# config.net
KiCad netlist of a schematic drawn in Altium Designer
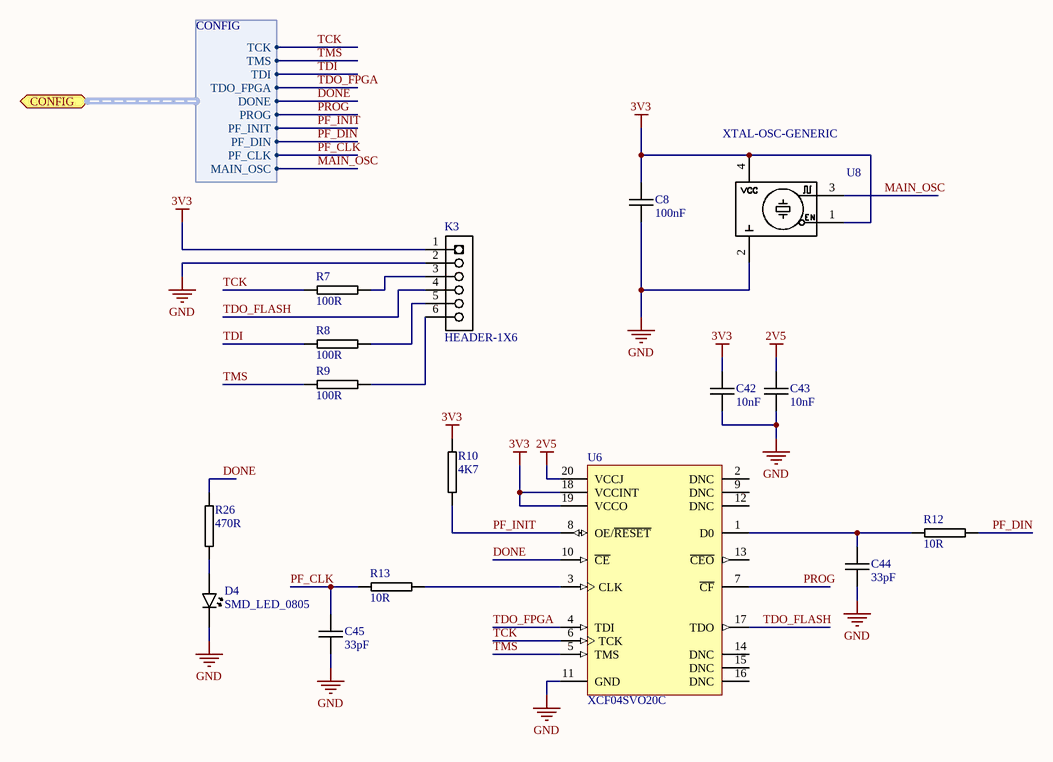
[diagram p0: config.SchDoc]

(export (version "E")
  (design (tool "Eeschema 10.0.6"))
  (components
    (comp (ref "C8")
      (value "100nF")
      (footprint "0603C-GENERIC")
      (description "GENERIC CAPACITOR NON POLARISED 0603")
      (fields (field (name "TOLERANCE") "±10%") (field (name "MANUFACTURER PART NUMBER") "C1608X7R1H103K"))
      (libsource (lib "vh_Altium Library") (part "0603C-100NF-50V-X7R-TDK"))
    )
    (comp (ref "C42")
      (value "10nF")
      (footprint "0603C-GENERIC")
      (description "GENERIC CAPACITOR NON POLARISED 0603")
      (fields
        (field (name "MANUFACTURER PART NUMBER") "GRM188R71H103KA01D")
        (field (name "MANUFACTURER") "Murata Electronics North America")
      )
      (libsource (lib "vh_Altium Library") (part "0603C-10NF-50V-X7R-MUR"))
    )
    (comp (ref "C43")
      (value "10nF")
      (footprint "0603C-GENERIC")
      (description "GENERIC CAPACITOR NON POLARISED 0603")
      (fields
        (field (name "MANUFACTURER PART NUMBER") "GRM188R71H103KA01D")
        (field (name "MANUFACTURER") "Murata Electronics North America")
      )
      (libsource (lib "vh_Altium Library") (part "0603C-10NF-50V-X7R-MUR"))
    )
    (comp (ref "C44")
      (value "33pF")
      (footprint "0603C-GENERIC")
      (description "GENERIC CAPACITOR NON POLARISED 0603")
      (libsource (lib "vh_Altium Library") (part "0603C-33PF-50V-C0G-PAN"))
    )
    (comp (ref "C45")
      (value "33pF")
      (footprint "0603C-GENERIC")
      (description "GENERIC CAPACITOR NON POLARISED 0603")
      (libsource (lib "vh_Altium Library") (part "0603C-33PF-50V-C0G-PAN"))
    )
    (comp (ref "D4")
      (value "SMD_LED_0805")
      (footprint "CD2012-0805")
      (libsource (lib "camera_board") (part "SMD_LED_0805"))
    )
    (comp (ref "K3")
      (value "HEADER-1X6")
      (footprint "HEADER-1X6")
      (libsource (lib "vh_Altium Library") (part "HEADER-1X6"))
    )
    (comp (ref "R7")
      (value "100R")
      (footprint "0603R-100")
      (description "RES 100 OHM 1/10W 1% 0603 SMD")
      (fields (field (name "MANUFACTURER PART NUMBER") "RMCF 1/16 100 1% R"))
      (libsource (lib "vh_Altium Library") (part "0603R-100"))
    )
    (comp (ref "R8")
      (value "100R")
      (footprint "0603R-100")
      (description "RES 100 OHM 1/10W 1% 0603 SMD")
      (fields (field (name "MANUFACTURER PART NUMBER") "RMCF 1/16 100 1% R"))
      (libsource (lib "vh_Altium Library") (part "0603R-100"))
    )
    (comp (ref "R9")
      (value "100R")
      (footprint "0603R-100")
      (description "RES 100 OHM 1/10W 1% 0603 SMD")
      (fields (field (name "MANUFACTURER PART NUMBER") "RMCF 1/16 100 1% R"))
      (libsource (lib "vh_Altium Library") (part "0603R-100"))
    )
    (comp (ref "R10")
      (value "4K7")
      (footprint "0603R-4K7")
      (description "GENERIC RESISTOR 0603")
      (fields
        (field (name "MANUFACTURER") "Stackpole Electronics Inc")
        (field (name "MANUFACTURER PART NUMBER") "RMCF 1/16 4.7K 1% R")
      )
      (libsource (lib "vh_Altium Library") (part "0603R-4K7"))
    )
    (comp (ref "R12")
      (value "10R")
      (footprint "0603R-10")
      (description "GENERIC RESISTOR 0603")
      (fields
        (field (name "MANUFACTURER PART NUMBER") "RMCF 1/16 10 1% R")
        (field (name "MANUFACTURER") "Stackpole Electronics Inc")
      )
      (libsource (lib "vh_Altium Library") (part "0603R-10R"))
    )
    (comp (ref "R13")
      (value "10R")
      (footprint "0603R-10")
      (description "GENERIC RESISTOR 0603")
      (fields
        (field (name "MANUFACTURER PART NUMBER") "RMCF 1/16 10 1% R")
        (field (name "MANUFACTURER") "Stackpole Electronics Inc")
      )
      (libsource (lib "vh_Altium Library") (part "0603R-10R"))
    )
    (comp (ref "R26")
      (value "470R")
      (footprint "0603R-470")
      (description "GENERIC RESISTOR 0603")
      (fields (field (name "MANUFACTURER PART NUMBER") "RMCF 1/16 470 1% R") (field (name "TOLERANCE") "±1%"))
      (libsource (lib "vh_Altium Library") (part "0603R-470"))
    )
    (comp (ref "U6")
      (value "XCF04SVO20C")
      (footprint "VO20_N")
      (fields (field (name "PUBLISHER") "Altium Limited"))
      (libsource (lib "Xilinx XCF") (part "XCF04SVO20C"))
    )
    (comp (ref "U8")
      (value "XTAL-OSC-GENERIC")
      (footprint "XOSC-5X7")
      (description "GENERIC CRYSTAL OSCILLATOR")
      (libsource (lib "vh_Altium Library") (part "XTAL-OSC-GENERIC"))
    )
  )
  (nets
    (net (code "2") (name "/DONE") (class "Default")
      (node (ref "R26") (pin "1") (pintype "passive"))
      (node (ref "U6") (pin "10") (pinfunction "~{CE}_10") (pintype "input"))
    )
    (net (code "3") (name "/MAIN_OSC") (class "Default")
      (node (ref "U8") (pin "3") (pinfunction "OUT_3") (pintype "passive"))
    )
    (net (code "4") (name "/PF_CLK") (class "Default")
      (node (ref "C45") (pin "1") (pintype "passive"))
      (node (ref "R13") (pin "1") (pintype "passive"))
    )
    (net (code "5") (name "/PF_DIN") (class "Default") (node (ref "R12") (pin "2") (pintype "passive")))
    (net (code "6") (name "/PF_INIT") (class "Default")
      (node (ref "R10") (pin "2") (pintype "passive"))
      (node (ref "U6") (pin "8") (pinfunction "OE/~{RESET}_8") (pintype "bidirectional"))
    )
    (net (code "7") (name "/PROG") (class "Default")
      (node (ref "U6") (pin "7") (pinfunction "~{CF}_7") (pintype "open_collector"))
    )
    (net (code "8") (name "/TCK") (class "Default")
      (node (ref "R7") (pin "1") (pintype "passive"))
      (node (ref "U6") (pin "6") (pinfunction "TCK_6") (pintype "input"))
    )
    (net (code "9") (name "/TDI") (class "Default") (node (ref "R8") (pin "1") (pintype "passive")))
    (net (code "10") (name "/TDO_FLASH") (class "Default")
      (node (ref "K3") (pin "4") (pintype "passive"))
      (node (ref "U6") (pin "17") (pinfunction "TDO_17") (pintype "output"))
    )
    (net (code "11") (name "/TDO_FPGA") (class "Default")
      (node (ref "U6") (pin "4") (pinfunction "TDI_4") (pintype "input"))
    )
    (net (code "12") (name "/TMS") (class "Default")
      (node (ref "R9") (pin "1") (pintype "passive"))
      (node (ref "U6") (pin "5") (pinfunction "TMS_5") (pintype "input"))
    )
    (net (code "14") (name "2V5") (class "Default")
      (node (ref "C43") (pin "1") (pintype "passive"))
      (node (ref "U6") (pin "20") (pinfunction "VCCJ_20") (pintype "power_in"))
    )
    (net (code "15") (name "3V3") (class "Default")
      (node (ref "C42") (pin "1") (pintype "passive"))
      (node (ref "C8") (pin "1") (pintype "passive"))
      (node (ref "K3") (pin "1") (pintype "passive"))
      (node (ref "R10") (pin "1") (pintype "passive"))
      (node (ref "U6") (pin "18") (pinfunction "VCCINT_18") (pintype "power_in"))
      (node (ref "U6") (pin "19") (pinfunction "VCCO_19") (pintype "power_in"))
      (node (ref "U8") (pin "1") (pinfunction "EN_1") (pintype "passive"))
      (node (ref "U8") (pin "4") (pinfunction "VCC_4") (pintype "passive"))
    )
    (net (code "16") (name "GND") (class "Default")
      (node (ref "C42") (pin "2") (pintype "passive"))
      (node (ref "C43") (pin "2") (pintype "passive"))
      (node (ref "C44") (pin "2") (pintype "passive"))
      (node (ref "C45") (pin "2") (pintype "passive"))
      (node (ref "C8") (pin "2") (pintype "passive"))
      (node (ref "D4") (pin "2") (pinfunction "K_2") (pintype "passive"))
      (node (ref "K3") (pin "2") (pintype "passive"))
      (node (ref "U6") (pin "11") (pinfunction "GND_11") (pintype "power_in"))
      (node (ref "U8") (pin "2") (pinfunction "GND_2") (pintype "passive"))
    )
    (net (code "17") (name "Net-(D4-A)") (class "Default")
      (node (ref "D4") (pin "1") (pinfunction "A_1") (pintype "passive"))
      (node (ref "R26") (pin "2") (pintype "passive"))
    )
    (net (code "18") (name "Net-(K3-Pad3)") (class "Default")
      (node (ref "K3") (pin "3") (pintype "passive"))
      (node (ref "R7") (pin "2") (pintype "passive"))
    )
    (net (code "19") (name "Net-(K3-Pad5)") (class "Default")
      (node (ref "K3") (pin "5") (pintype "passive"))
      (node (ref "R8") (pin "2") (pintype "passive"))
    )
    (net (code "20") (name "Net-(K3-Pad6)") (class "Default")
      (node (ref "K3") (pin "6") (pintype "passive"))
      (node (ref "R9") (pin "2") (pintype "passive"))
    )
    (net (code "21") (name "Net-(U6-CLK)") (class "Default")
      (node (ref "R13") (pin "2") (pintype "passive"))
      (node (ref "U6") (pin "3") (pinfunction "CLK_3") (pintype "input"))
    )
    (net (code "22") (name "Net-(U6-D0)") (class "Default")
      (node (ref "C44") (pin "1") (pintype "passive"))
      (node (ref "R12") (pin "1") (pintype "passive"))
      (node (ref "U6") (pin "1") (pinfunction "D0_1") (pintype "tri_state"))
    )
    (net (code "23") (name "unconnected-(U6-DNC-Pad2)") (class "Default")
      (node (ref "U6") (pin "2") (pinfunction "DNC_2") (pintype "passive"))
    )
    (net (code "24") (name "unconnected-(U6-DNC-Pad9)") (class "Default")
      (node (ref "U6") (pin "9") (pinfunction "DNC_9") (pintype "passive"))
    )
    (net (code "25") (name "unconnected-(U6-DNC-Pad12)") (class "Default")
      (node (ref "U6") (pin "12") (pinfunction "DNC_12") (pintype "passive"))
    )
    (net (code "26") (name "unconnected-(U6-DNC-Pad14)") (class "Default")
      (node (ref "U6") (pin "14") (pinfunction "DNC_14") (pintype "passive"))
    )
    (net (code "27") (name "unconnected-(U6-DNC-Pad15)") (class "Default")
      (node (ref "U6") (pin "15") (pinfunction "DNC_15") (pintype "passive"))
    )
    (net (code "28") (name "unconnected-(U6-DNC-Pad16)") (class "Default")
      (node (ref "U6") (pin "16") (pinfunction "DNC_16") (pintype "passive"))
    )
    (net (code "29") (name "unconnected-(U6-~{CEO}-Pad13)") (class "Default")
      (node (ref "U6") (pin "13") (pinfunction "~{CEO}_13") (pintype "output"))
    )
  )
)
